# nRF52840.net
KiCad netlist of a schematic drawn in Altium Designer
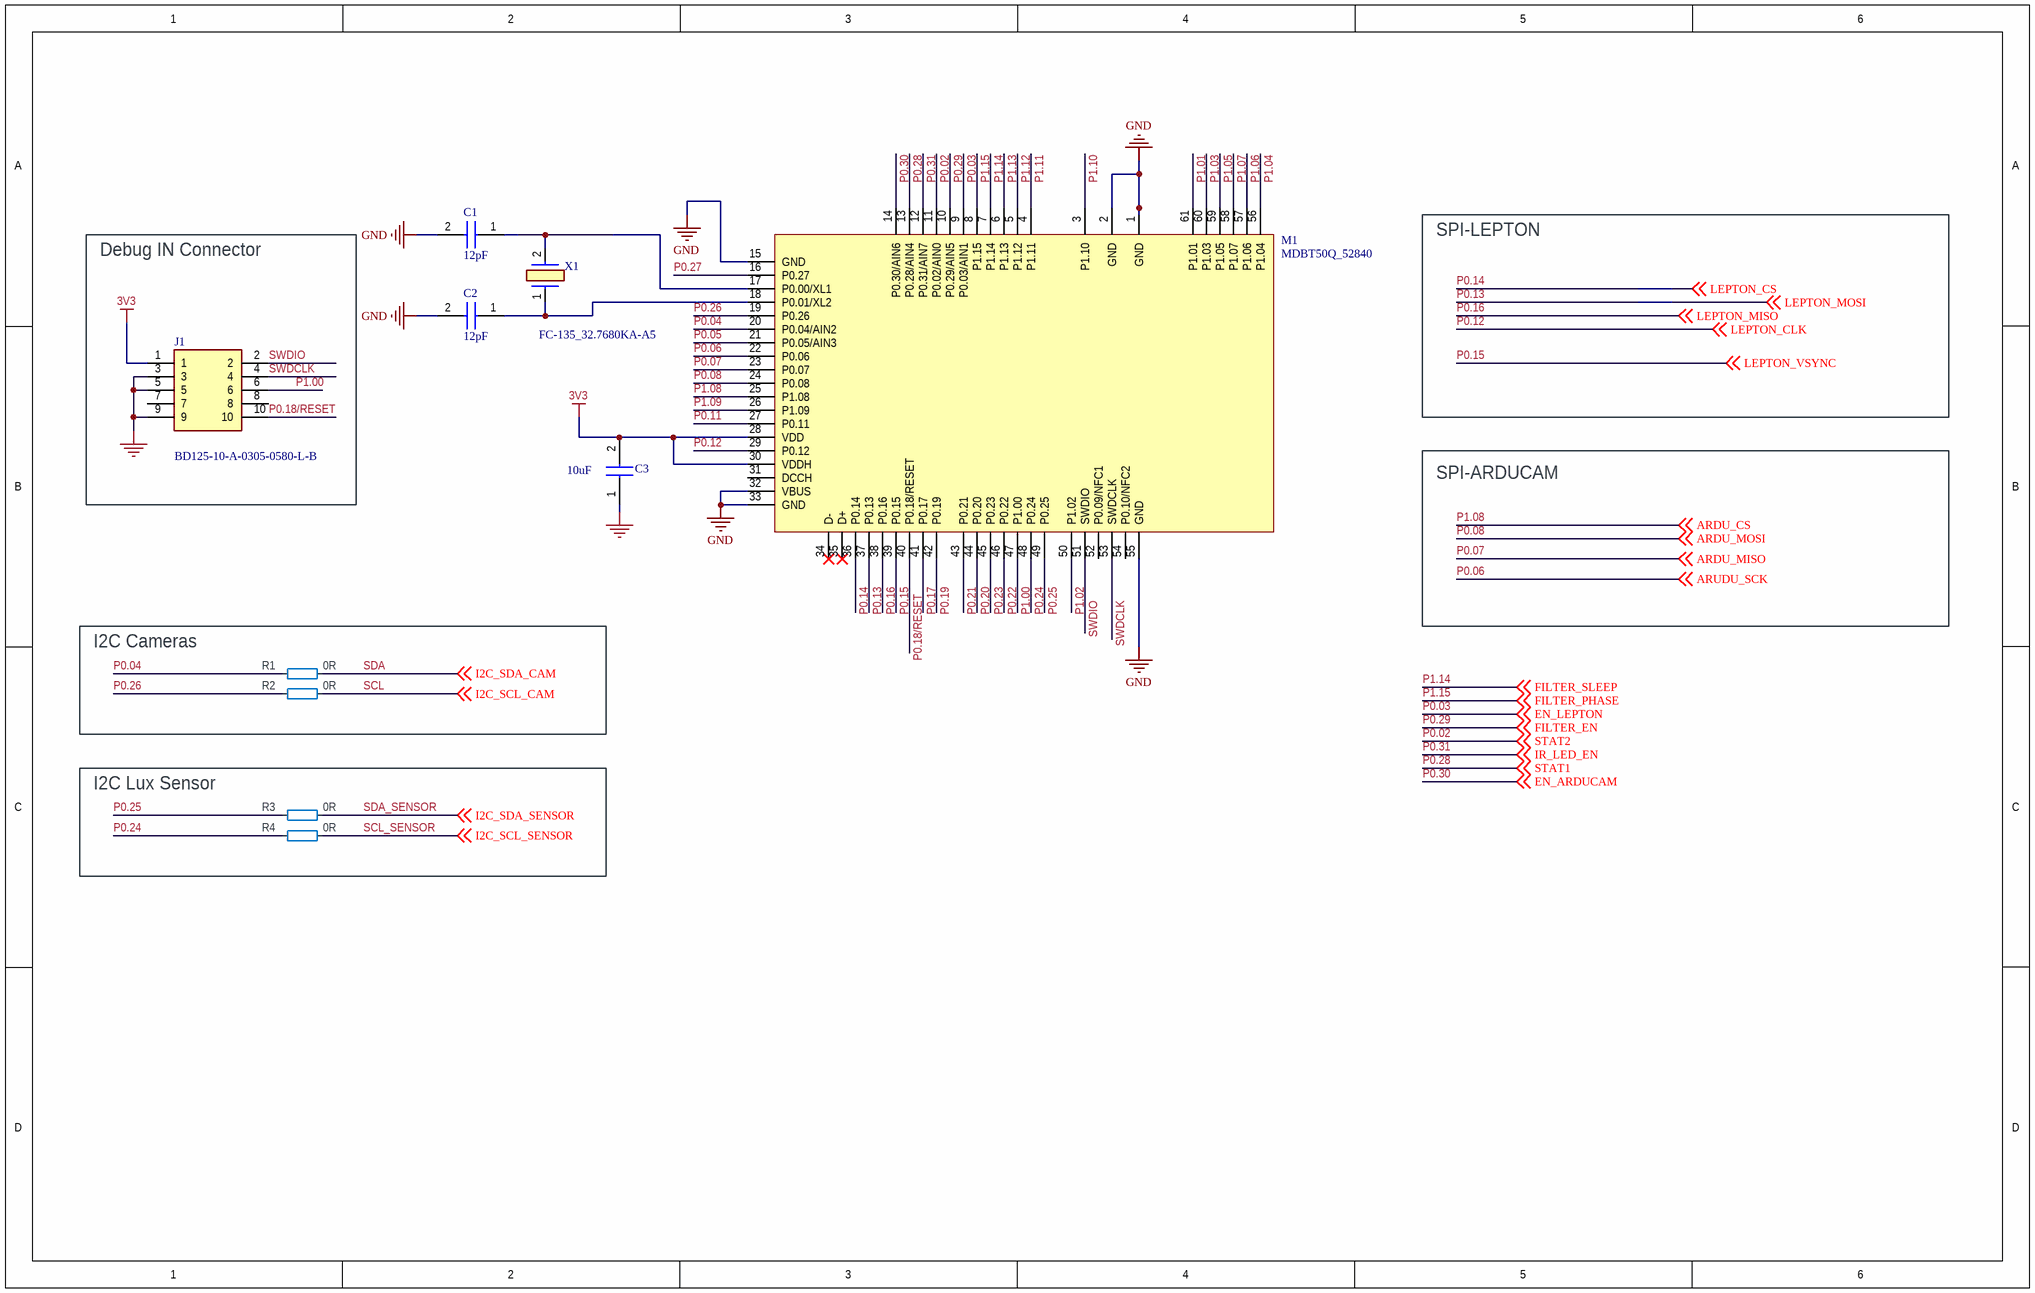
[diagram p0: nRF52840.SchDoc]

(export (version "E")
  (design (tool "Eeschema 10.0.6"))
  (components
    (comp (ref "C1")
      (value "12pF")
      (footprint "SamacSys:CAPC1608X90N")
      (description "0603 CAP X5R 25V")
      (fields
        (field (name "MANUFACTURER_PART_NUMBER") "CC0603KRX7R0BB104")
        (field (name "MOUSER PART NUMBER") "603-CC603KRX7R0BB104")
      )
      (libsource (lib "*") (part "CC0603KRX7R0BB104"))
    )
    (comp (ref "C2")
      (value "12pF")
      (footprint "SamacSys:CAPC1608X90N")
      (description "0603 CAP X5R 25V")
      (fields
        (field (name "MANUFACTURER_PART_NUMBER") "CC0603KRX7R0BB104")
        (field (name "MOUSER PART NUMBER") "603-CC603KRX7R0BB104")
      )
      (libsource (lib "*") (part "CC0603KRX7R0BB104"))
    )
    (comp (ref "C3")
      (value "10uF")
      (footprint "SamacSys:CAPC1608X90N")
      (description "0603 CAP X5R 25V")
      (fields
        (field (name "MANUFACTURER_PART_NUMBER") "CC0603KRX7R0BB104")
        (field (name "MOUSER PART NUMBER") "603-CC603KRX7R0BB104")
      )
      (libsource (lib "*") (part "CC0603KRX7R0BB104"))
    )
    (comp (ref "J1")
      (value "BD125-10-A-0305-0580-L-B")
      (footprint "SamacSys:BD12510A03050580LB")
      (description "Connector")
      (fields (field (name "MOUSER PART NUMBER") "640-BD12510A305580LB"))
      (libsource (lib "*") (part "BD125-10-A-0305-0580-L-B"))
    )
    (comp (ref "M1")
      (value "MDBT50Q_52840")
      (footprint "MDBT50Q")
      (description "MDBT50Q(52840)")
      (libsource (lib "SamacSys") (part "MDBT50Q_52840"))
    )
    (comp (ref "R1")
      (value "0R")
      (footprint "RESC0603X03L_C")
      (description "Resistor, ±5%, 1/10W 0603")
      (fields
        (field (name "PART NUMBER") "R0201-0R")
        (field (name "MANUFACTURER") "N.A.")
        (field (name "AUTHOR") "rsk")
      )
      (libsource (lib "pca10056") (part "RES"))
    )
    (comp (ref "R2")
      (value "0R")
      (footprint "RESC0603X03L_C")
      (description "Resistor, ±5%, 1/10W 0603")
      (fields
        (field (name "PART NUMBER") "R0201-0R")
        (field (name "MANUFACTURER") "N.A.")
        (field (name "AUTHOR") "rsk")
      )
      (libsource (lib "pca10056") (part "RES"))
    )
    (comp (ref "R3")
      (value "0R")
      (footprint "RESC0603X03L_C")
      (description "Resistor, ±5%, 1/10W 0603")
      (fields
        (field (name "PART NUMBER") "R0201-0R")
        (field (name "MANUFACTURER") "N.A.")
        (field (name "AUTHOR") "rsk")
      )
      (libsource (lib "pca10056") (part "RES"))
    )
    (comp (ref "R4")
      (value "0R")
      (footprint "RESC0603X03L_C")
      (description "Resistor, ±5%, 1/10W 0603")
      (fields
        (field (name "PART NUMBER") "R0201-0R")
        (field (name "MANUFACTURER") "N.A.")
        (field (name "AUTHOR") "rsk")
      )
      (libsource (lib "pca10056") (part "RES"))
    )
    (comp (ref "X1")
      (value "FC-135_32.7680KA-A5")
      (footprint "SamacSys:FC135327680KAA5")
      (description "Crystal or Oscillator")
      (fields
        (field (name "MANUFACTURER_PART_NUMBER") "FC-135 32.7680KA-A5")
        (field (name "MOUSER PART NUMBER") "732-532.7680KA-A5")
      )
      (libsource (lib "*") (part "FC-135_32.7680KA-A5"))
    )
  )
  (nets
    (net (code "1") (name "/P0.04") (class "Default")
      (node (ref "M1") (pin "20") (pinfunction "P0.04/AIN2_20") (pintype "passive"))
      (node (ref "R1") (pin "2") (pinfunction "2_2") (pintype "passive"))
    )
    (net (code "2") (name "/P0.05") (class "Default")
      (node (ref "M1") (pin "21") (pinfunction "P0.05/AIN3_21") (pintype "passive"))
    )
    (net (code "3") (name "/P0.11") (class "Default")
      (node (ref "M1") (pin "27") (pinfunction "P0.11_27") (pintype "passive"))
    )
    (net (code "4") (name "/P0.17") (class "Default")
      (node (ref "M1") (pin "41") (pinfunction "P0.17_41") (pintype "passive"))
    )
    (net (code "5") (name "/P0.18{slash}RESET") (class "Default")
      (node (ref "J1") (pin "10") (pinfunction "10_10") (pintype "passive"))
      (node (ref "M1") (pin "40") (pinfunction "P0.18/RESET_40") (pintype "passive"))
    )
    (net (code "6") (name "/P0.19") (class "Default")
      (node (ref "M1") (pin "42") (pinfunction "P0.19_42") (pintype "passive"))
    )
    (net (code "7") (name "/P0.20") (class "Default")
      (node (ref "M1") (pin "44") (pinfunction "P0.20_44") (pintype "passive"))
    )
    (net (code "8") (name "/P0.21") (class "Default")
      (node (ref "M1") (pin "43") (pinfunction "P0.21_43") (pintype "passive"))
    )
    (net (code "9") (name "/P0.22") (class "Default")
      (node (ref "M1") (pin "46") (pinfunction "P0.22_46") (pintype "passive"))
    )
    (net (code "10") (name "/P0.23") (class "Default")
      (node (ref "M1") (pin "45") (pinfunction "P0.23_45") (pintype "passive"))
    )
    (net (code "11") (name "/P0.24") (class "Default")
      (node (ref "M1") (pin "48") (pinfunction "P0.24_48") (pintype "passive"))
      (node (ref "R4") (pin "2") (pinfunction "2_2") (pintype "passive"))
    )
    (net (code "12") (name "/P0.25") (class "Default")
      (node (ref "M1") (pin "49") (pinfunction "P0.25_49") (pintype "passive"))
      (node (ref "R3") (pin "2") (pinfunction "2_2") (pintype "passive"))
    )
    (net (code "13") (name "/P0.26") (class "Default")
      (node (ref "M1") (pin "19") (pinfunction "P0.26_19") (pintype "passive"))
      (node (ref "R2") (pin "2") (pinfunction "2_2") (pintype "passive"))
    )
    (net (code "14") (name "/P0.27") (class "Default")
      (node (ref "M1") (pin "16") (pinfunction "P0.27_16") (pintype "passive"))
    )
    (net (code "15") (name "/P1.00") (class "Default")
      (node (ref "J1") (pin "6") (pinfunction "6_6") (pintype "passive"))
      (node (ref "M1") (pin "47") (pinfunction "P1.00_47") (pintype "passive"))
    )
    (net (code "16") (name "/P1.01") (class "Default")
      (node (ref "M1") (pin "61") (pinfunction "P1.01_61") (pintype "passive"))
    )
    (net (code "17") (name "/P1.02") (class "Default")
      (node (ref "M1") (pin "50") (pinfunction "P1.02_50") (pintype "passive"))
    )
    (net (code "18") (name "/P1.03") (class "Default")
      (node (ref "M1") (pin "60") (pinfunction "P1.03_60") (pintype "passive"))
    )
    (net (code "19") (name "/P1.04") (class "Default")
      (node (ref "M1") (pin "56") (pinfunction "P1.04_56") (pintype "passive"))
    )
    (net (code "20") (name "/P1.05") (class "Default")
      (node (ref "M1") (pin "59") (pinfunction "P1.05_59") (pintype "passive"))
    )
    (net (code "21") (name "/P1.06") (class "Default")
      (node (ref "M1") (pin "57") (pinfunction "P1.06_57") (pintype "passive"))
    )
    (net (code "22") (name "/P1.07") (class "Default")
      (node (ref "M1") (pin "58") (pinfunction "P1.07_58") (pintype "passive"))
    )
    (net (code "23") (name "/P1.09") (class "Default")
      (node (ref "M1") (pin "26") (pinfunction "P1.09_26") (pintype "passive"))
    )
    (net (code "24") (name "/P1.10") (class "Default")
      (node (ref "M1") (pin "3") (pinfunction "P1.10_3") (pintype "passive"))
    )
    (net (code "25") (name "/P1.11") (class "Default")
      (node (ref "M1") (pin "4") (pinfunction "P1.11_4") (pintype "passive"))
    )
    (net (code "26") (name "/P1.12") (class "Default")
      (node (ref "M1") (pin "5") (pinfunction "P1.12_5") (pintype "passive"))
    )
    (net (code "27") (name "/P1.13") (class "Default")
      (node (ref "M1") (pin "6") (pinfunction "P1.13_6") (pintype "passive"))
    )
    (net (code "28") (name "/SWDCLK") (class "Default")
      (node (ref "J1") (pin "4") (pinfunction "4_4") (pintype "passive"))
      (node (ref "M1") (pin "53") (pinfunction "SWDCLK_53") (pintype "passive"))
    )
    (net (code "29") (name "/SWDIO") (class "Default")
      (node (ref "J1") (pin "2") (pinfunction "2_2") (pintype "passive"))
      (node (ref "M1") (pin "51") (pinfunction "SWDIO_51") (pintype "passive"))
    )
    (net (code "30") (name "3V3") (class "Default")
      (node (ref "C3") (pin "2") (pinfunction "2_2") (pintype "passive"))
      (node (ref "J1") (pin "1") (pinfunction "1_1") (pintype "passive"))
      (node (ref "M1") (pin "28") (pinfunction "VDD_28") (pintype "passive"))
      (node (ref "M1") (pin "30") (pinfunction "VDDH_30") (pintype "passive"))
    )
    (net (code "31") (name "ARDU_CS") (class "Default")
      (node (ref "M1") (pin "25") (pinfunction "P1.08_25") (pintype "passive"))
    )
    (net (code "32") (name "ARDU_MISO") (class "Default")
      (node (ref "M1") (pin "23") (pinfunction "P0.07_23") (pintype "passive"))
    )
    (net (code "33") (name "ARDU_MOSI") (class "Default")
      (node (ref "M1") (pin "24") (pinfunction "P0.08_24") (pintype "passive"))
    )
    (net (code "34") (name "ARUDU_SCK") (class "Default")
      (node (ref "M1") (pin "22") (pinfunction "P0.06_22") (pintype "passive"))
    )
    (net (code "35") (name "EN_ARDUCAM") (class "Default")
      (node (ref "M1") (pin "14") (pinfunction "P0.30/AIN6_14") (pintype "passive"))
    )
    (net (code "36") (name "EN_LEPTON") (class "Default")
      (node (ref "M1") (pin "9") (pinfunction "P0.03/AIN1_9") (pintype "passive"))
    )
    (net (code "37") (name "FILTER_EN") (class "Default")
      (node (ref "M1") (pin "10") (pinfunction "P0.29/AIN5_10") (pintype "passive"))
    )
    (net (code "38") (name "FILTER_PHASE") (class "Default")
      (node (ref "M1") (pin "8") (pinfunction "P1.15_8") (pintype "passive"))
    )
    (net (code "39") (name "FILTER_SLEEP") (class "Default")
      (node (ref "M1") (pin "7") (pinfunction "P1.14_7") (pintype "passive"))
    )
    (net (code "40") (name "GND") (class "Default")
      (node (ref "C1") (pin "2") (pinfunction "2_2") (pintype "passive"))
      (node (ref "C2") (pin "2") (pinfunction "2_2") (pintype "passive"))
      (node (ref "C3") (pin "1") (pinfunction "1_1") (pintype "passive"))
      (node (ref "J1") (pin "3") (pinfunction "3_3") (pintype "passive"))
      (node (ref "J1") (pin "5") (pinfunction "5_5") (pintype "passive"))
      (node (ref "J1") (pin "9") (pinfunction "9_9") (pintype "passive"))
      (node (ref "M1") (pin "1") (pinfunction "GND_1") (pintype "passive"))
      (node (ref "M1") (pin "15") (pinfunction "GND_15") (pintype "passive"))
      (node (ref "M1") (pin "2") (pinfunction "GND_2") (pintype "passive"))
      (node (ref "M1") (pin "32") (pinfunction "VBUS_32") (pintype "passive"))
      (node (ref "M1") (pin "33") (pinfunction "GND_33") (pintype "passive"))
      (node (ref "M1") (pin "55") (pinfunction "GND_55") (pintype "passive"))
    )
    (net (code "41") (name "I2C_SCL_CAM") (class "Default")
      (node (ref "R2") (pin "1") (pinfunction "1_1") (pintype "passive"))
    )
    (net (code "42") (name "I2C_SCL_SENSOR") (class "Default")
      (node (ref "R4") (pin "1") (pinfunction "1_1") (pintype "passive"))
    )
    (net (code "43") (name "I2C_SDA_CAM") (class "Default")
      (node (ref "R1") (pin "1") (pinfunction "1_1") (pintype "passive"))
    )
    (net (code "44") (name "I2C_SDA_SENSOR") (class "Default")
      (node (ref "R3") (pin "1") (pinfunction "1_1") (pintype "passive"))
    )
    (net (code "45") (name "IR_LED_EN") (class "Default")
      (node (ref "M1") (pin "12") (pinfunction "P0.31/AIN7_12") (pintype "passive"))
    )
    (net (code "46") (name "LEPTON_CLK") (class "Default")
      (node (ref "M1") (pin "29") (pinfunction "P0.12_29") (pintype "passive"))
    )
    (net (code "47") (name "LEPTON_CS") (class "Default")
      (node (ref "M1") (pin "36") (pinfunction "P0.14_36") (pintype "passive"))
    )
    (net (code "48") (name "LEPTON_MISO") (class "Default")
      (node (ref "M1") (pin "38") (pinfunction "P0.16_38") (pintype "passive"))
    )
    (net (code "49") (name "LEPTON_MOSI") (class "Default")
      (node (ref "M1") (pin "37") (pinfunction "P0.13_37") (pintype "passive"))
    )
    (net (code "50") (name "LEPTON_VSYNC") (class "Default")
      (node (ref "M1") (pin "39") (pinfunction "P0.15_39") (pintype "passive"))
    )
    (net (code "51") (name "Net-(M1-P0.00{slash}XL1)") (class "Default")
      (node (ref "C1") (pin "1") (pinfunction "1_1") (pintype "passive"))
      (node (ref "M1") (pin "17") (pinfunction "P0.00/XL1_17") (pintype "passive"))
      (node (ref "X1") (pin "2") (pinfunction "2_2") (pintype "passive"))
    )
    (net (code "52") (name "Net-(M1-P0.01{slash}XL2)") (class "Default")
      (node (ref "C2") (pin "1") (pinfunction "1_1") (pintype "passive"))
      (node (ref "M1") (pin "18") (pinfunction "P0.01/XL2_18") (pintype "passive"))
      (node (ref "X1") (pin "1") (pinfunction "1_1") (pintype "passive"))
    )
    (net (code "53") (name "STAT1") (class "Default")
      (node (ref "M1") (pin "13") (pinfunction "P0.28/AIN4_13") (pintype "passive"))
    )
    (net (code "54") (name "STAT2") (class "Default")
      (node (ref "M1") (pin "11") (pinfunction "P0.02/AIN0_11") (pintype "passive"))
    )
    (net (code "55") (name "unconnected-(J1-Pad7)") (class "Default")
      (node (ref "J1") (pin "7") (pinfunction "7_7") (pintype "passive"))
    )
    (net (code "56") (name "unconnected-(J1-Pad8)") (class "Default")
      (node (ref "J1") (pin "8") (pinfunction "8_8") (pintype "passive"))
    )
    (net (code "57") (name "unconnected-(M1-D+-Pad35)") (class "Default")
      (node (ref "M1") (pin "35") (pinfunction "D+_35") (pintype "passive+no_connect"))
    )
    (net (code "58") (name "unconnected-(M1-D--Pad34)") (class "Default")
      (node (ref "M1") (pin "34") (pinfunction "D-_34") (pintype "passive+no_connect"))
    )
    (net (code "59") (name "unconnected-(M1-DCCH-Pad31)") (class "Default")
      (node (ref "M1") (pin "31") (pinfunction "DCCH_31") (pintype "passive"))
    )
    (net (code "60") (name "unconnected-(M1-P0.09{slash}NFC1-Pad52)") (class "Default")
      (node (ref "M1") (pin "52") (pinfunction "P0.09/NFC1_52") (pintype "passive"))
    )
    (net (code "61") (name "unconnected-(M1-P0.10{slash}NFC2-Pad54)") (class "Default")
      (node (ref "M1") (pin "54") (pinfunction "P0.10/NFC2_54") (pintype "passive"))
    )
  )
)
